# Schematic_SmartHome.net
KiCad netlist of a schematic drawn in EasyEDA
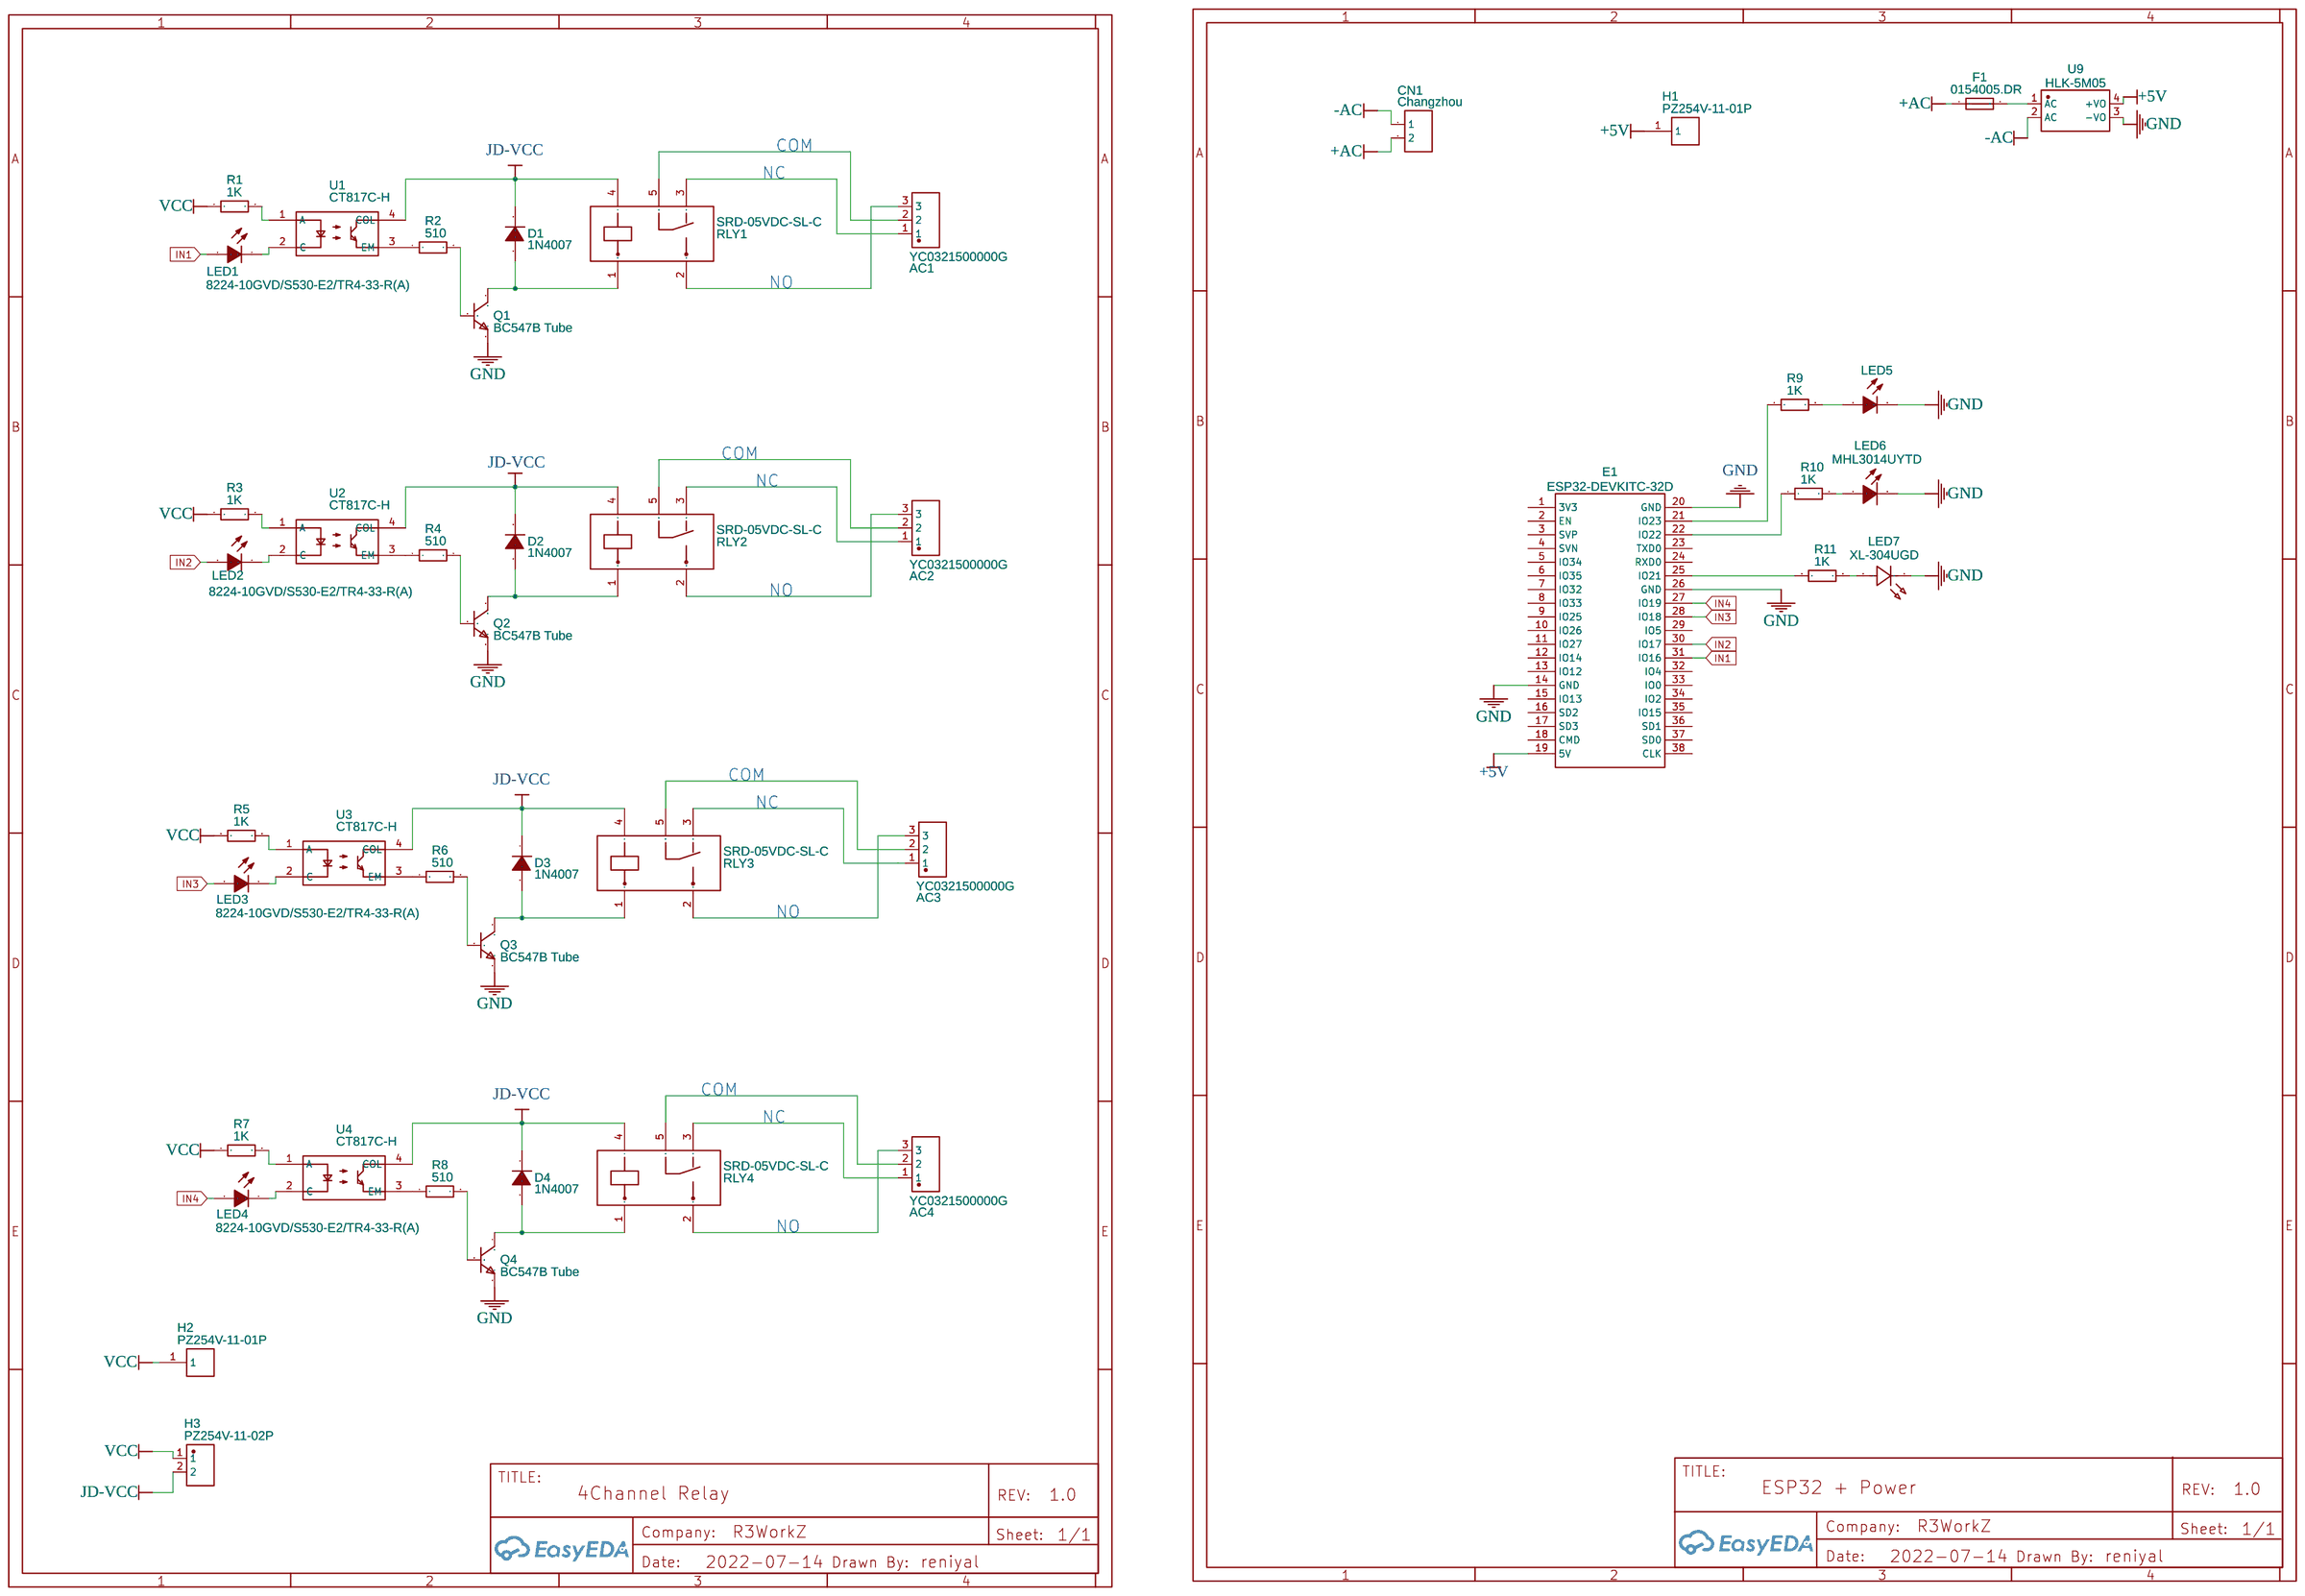
[diagram p0: schematic sheet]

(export (version "E")
  (design (tool "Eeschema 10.0.6"))
  (components
    (comp (ref "AC1")
      (value "YC0321500000G")
      (fields (field (name "BOM_Supplier Part") "C2683166"))
      (libsource (lib "") (part "YC0321500000G"))
    )
    (comp (ref "AC2")
      (value "YC0321500000G")
      (fields (field (name "BOM_Supplier Part") "C2683166"))
      (libsource (lib "") (part "YC0321500000G"))
    )
    (comp (ref "AC3")
      (value "YC0321500000G")
      (fields (field (name "BOM_Supplier Part") "C2683166"))
      (libsource (lib "") (part "YC0321500000G"))
    )
    (comp (ref "AC4")
      (value "YC0321500000G")
      (fields (field (name "BOM_Supplier Part") "C2683166"))
      (libsource (lib "") (part "YC0321500000G"))
    )
    (comp (ref "CN1")
      (value "Changzhou")
      (fields (field (name "BOM_Manufacturer Part") "XT30UPB-F") (field (name "BOM_Supplier Part") "C108769"))
      (libsource (lib "") (part "XT30UPB-F"))
    )
    (comp (ref "D1")
      (value "1N4007")
      (fields (field (name "BOM_Supplier Part") "C106903"))
      (libsource (lib "") (part "1N4007"))
    )
    (comp (ref "D2")
      (value "1N4007")
      (fields (field (name "BOM_Supplier Part") "C106903"))
      (libsource (lib "") (part "1N4007"))
    )
    (comp (ref "D3")
      (value "1N4007")
      (fields (field (name "BOM_Supplier Part") "C106903"))
      (libsource (lib "") (part "1N4007"))
    )
    (comp (ref "D4")
      (value "1N4007")
      (fields (field (name "BOM_Supplier Part") "C106903"))
      (libsource (lib "") (part "1N4007"))
    )
    (comp (ref "E1") (value "ESP32-DEVKITC-32D") (libsource (lib "") (part "ESP32-DEVKITC-32D")))
    (comp (ref "F1")
      (value "0154005.DR")
      (fields (field (name "BOM_Supplier Part") "C206916"))
      (libsource (lib "") (part "0154005.DR"))
    )
    (comp (ref "H1")
      (value "PZ254V-11-01P")
      (fields (field (name "BOM_Supplier Part") "C492400"))
      (libsource (lib "") (part "PZ254V-11-01P"))
    )
    (comp (ref "H2")
      (value "PZ254V-11-01P")
      (fields (field (name "BOM_Supplier Part") "C492400"))
      (libsource (lib "") (part "PZ254V-11-01P"))
    )
    (comp (ref "H3")
      (value "PZ254V-11-02P")
      (fields (field (name "BOM_Supplier Part") "C492401"))
      (libsource (lib "") (part "PZ254V-11-02P"))
    )
    (comp (ref "LED1")
      (value "8224-10GVD/S530-E2/TR4-33-R(A)")
      (fields (field (name "BOM_Supplier Part") "C329173"))
      (libsource (lib "") (part "8224-10GVD/S530-E2/TR4-33-R(A)"))
    )
    (comp (ref "LED2")
      (value "8224-10GVD/S530-E2/TR4-33-R(A)")
      (fields (field (name "BOM_Supplier Part") "C329173"))
      (libsource (lib "") (part "8224-10GVD/S530-E2/TR4-33-R(A)"))
    )
    (comp (ref "LED3")
      (value "8224-10GVD/S530-E2/TR4-33-R(A)")
      (fields (field (name "BOM_Supplier Part") "C329173"))
      (libsource (lib "") (part "8224-10GVD/S530-E2/TR4-33-R(A)"))
    )
    (comp (ref "LED4")
      (value "8224-10GVD/S530-E2/TR4-33-R(A)")
      (fields (field (name "BOM_Supplier Part") "C329173"))
      (libsource (lib "") (part "8224-10GVD/S530-E2/TR4-33-R(A)"))
    )
    (comp (ref "LED5")
      (value "8224-10GVD/S530-E2/TR4-33-R(A)")
      (fields (field (name "BOM_Supplier Part") "C329173"))
      (libsource (lib "") (part "8224-10GVD/S530-E2/TR4-33-R(A)"))
    )
    (comp (ref "LED6")
      (value "MHL3014UYTD")
      (fields (field (name "BOM_Supplier Part") "C409800"))
      (libsource (lib "") (part "MHL3014UYTD"))
    )
    (comp (ref "LED7")
      (value "XL-304UGD")
      (fields (field (name "BOM_Supplier Part") "C2895477"))
      (libsource (lib "") (part "XL-304UGD"))
    )
    (comp (ref "Q1")
      (value "BC547B Tube")
      (fields (field (name "BOM_Supplier Part") "C2092"))
      (libsource (lib "") (part "BC547B Tube"))
    )
    (comp (ref "Q2")
      (value "BC547B Tube")
      (fields (field (name "BOM_Supplier Part") "C2092"))
      (libsource (lib "") (part "BC547B Tube"))
    )
    (comp (ref "Q3")
      (value "BC547B Tube")
      (fields (field (name "BOM_Supplier Part") "C2092"))
      (libsource (lib "") (part "BC547B Tube"))
    )
    (comp (ref "Q4")
      (value "BC547B Tube")
      (fields (field (name "BOM_Supplier Part") "C2092"))
      (libsource (lib "") (part "BC547B Tube"))
    )
    (comp (ref "R1")
      (value "1K")
      (fields
        (field (name "BOM_Manufacturer Part") "MFR0W4F1001A50")
        (field (name "BOM_Supplier Part") "C57435")
      )
      (libsource (lib "") (part "MFR0W4F1001A50"))
    )
    (comp (ref "R2")
      (value "510")
      (fields
        (field (name "BOM_Manufacturer Part") "RNU18F5100A520NH")
        (field (name "BOM_Supplier Part") "C274431")
      )
      (libsource (lib "") (part "RNU18F5100A520NH"))
    )
    (comp (ref "R3")
      (value "1K")
      (fields
        (field (name "BOM_Manufacturer Part") "MFR0W4F1001A50")
        (field (name "BOM_Supplier Part") "C57435")
      )
      (libsource (lib "") (part "MFR0W4F1001A50"))
    )
    (comp (ref "R4")
      (value "510")
      (fields
        (field (name "BOM_Manufacturer Part") "RNU18F5100A520NH")
        (field (name "BOM_Supplier Part") "C274431")
      )
      (libsource (lib "") (part "RNU18F5100A520NH"))
    )
    (comp (ref "R5")
      (value "1K")
      (fields
        (field (name "BOM_Manufacturer Part") "MFR0W4F1001A50")
        (field (name "BOM_Supplier Part") "C57435")
      )
      (libsource (lib "") (part "MFR0W4F1001A50"))
    )
    (comp (ref "R6")
      (value "510")
      (fields
        (field (name "BOM_Manufacturer Part") "RNU18F5100A520NH")
        (field (name "BOM_Supplier Part") "C274431")
      )
      (libsource (lib "") (part "RNU18F5100A520NH"))
    )
    (comp (ref "R7")
      (value "1K")
      (fields
        (field (name "BOM_Manufacturer Part") "MFR0W4F1001A50")
        (field (name "BOM_Supplier Part") "C57435")
      )
      (libsource (lib "") (part "MFR0W4F1001A50"))
    )
    (comp (ref "R8")
      (value "510")
      (fields
        (field (name "BOM_Manufacturer Part") "RNU18F5100A520NH")
        (field (name "BOM_Supplier Part") "C274431")
      )
      (libsource (lib "") (part "RNU18F5100A520NH"))
    )
    (comp (ref "R9")
      (value "1K")
      (fields
        (field (name "BOM_Manufacturer Part") "MFR0W4F1001A50")
        (field (name "BOM_Supplier Part") "C57435")
      )
      (libsource (lib "") (part "MFR0W4F1001A50"))
    )
    (comp (ref "R10")
      (value "1K")
      (fields
        (field (name "BOM_Manufacturer Part") "MFR0W4F1001A50")
        (field (name "BOM_Supplier Part") "C57435")
      )
      (libsource (lib "") (part "MFR0W4F1001A50"))
    )
    (comp (ref "R11")
      (value "1K")
      (fields
        (field (name "BOM_Manufacturer Part") "MFR0W4F1001A50")
        (field (name "BOM_Supplier Part") "C57435")
      )
      (libsource (lib "") (part "MFR0W4F1001A50"))
    )
    (comp (ref "RLY1")
      (value "SRD-05VDC-SL-C")
      (fields (field (name "BOM_Supplier Part") "C35449"))
      (libsource (lib "") (part "SRD-05VDC-SL-C"))
    )
    (comp (ref "RLY2")
      (value "SRD-05VDC-SL-C")
      (fields (field (name "BOM_Supplier Part") "C35449"))
      (libsource (lib "") (part "SRD-05VDC-SL-C"))
    )
    (comp (ref "RLY3")
      (value "SRD-05VDC-SL-C")
      (fields (field (name "BOM_Supplier Part") "C35449"))
      (libsource (lib "") (part "SRD-05VDC-SL-C"))
    )
    (comp (ref "RLY4")
      (value "SRD-05VDC-SL-C")
      (fields (field (name "BOM_Supplier Part") "C35449"))
      (libsource (lib "") (part "SRD-05VDC-SL-C"))
    )
    (comp (ref "U1")
      (value "CT817C-H")
      (fields (field (name "BOM_Supplier Part") "C127188"))
      (libsource (lib "") (part "CT817C-H"))
    )
    (comp (ref "U2")
      (value "CT817C-H")
      (fields (field (name "BOM_Supplier Part") "C127188"))
      (libsource (lib "") (part "CT817C-H"))
    )
    (comp (ref "U3")
      (value "CT817C-H")
      (fields (field (name "BOM_Supplier Part") "C127188"))
      (libsource (lib "") (part "CT817C-H"))
    )
    (comp (ref "U4")
      (value "CT817C-H")
      (fields (field (name "BOM_Supplier Part") "C127188"))
      (libsource (lib "") (part "CT817C-H"))
    )
    (comp (ref "U9")
      (value "HLK-5M05")
      (fields (field (name "BOM_Supplier Part") "C209907"))
      (libsource (lib "") (part "HLK-5M05"))
    )
  )
  (nets
    (net (code "1") (name "+5V") (class "Default")
      (node (ref "E1") (pin "19") (pinfunction "5V_19") (pintype "unspecified"))
      (node (ref "H1") (pin "1") (pinfunction "1_1") (pintype "unspecified"))
      (node (ref "U9") (pin "4") (pinfunction "+VO_4") (pintype "unspecified"))
    )
    (net (code "2") (name "+AC") (class "Default")
      (node (ref "CN1") (pin "2") (pinfunction "2_2") (pintype "unspecified"))
      (node (ref "F1") (pin "1") (pinfunction "1_1") (pintype "unspecified"))
    )
    (net (code "3") (name "-AC") (class "Default")
      (node (ref "CN1") (pin "1") (pinfunction "1_1") (pintype "unspecified"))
      (node (ref "U9") (pin "2") (pinfunction "AC_2") (pintype "unspecified"))
    )
    (net (code "4") (name "GND") (class "Default")
      (node (ref "E1") (pin "14") (pinfunction "GND_14") (pintype "unspecified"))
      (node (ref "E1") (pin "20") (pinfunction "GND_20") (pintype "unspecified"))
      (node (ref "E1") (pin "26") (pinfunction "GND_26") (pintype "unspecified"))
      (node (ref "LED5") (pin "1") (pinfunction "K_1") (pintype "input"))
      (node (ref "LED6") (pin "2") (pinfunction "-_2") (pintype "unspecified"))
      (node (ref "LED7") (pin "2") (pinfunction "K_2") (pintype "unspecified"))
      (node (ref "Q1") (pin "3") (pinfunction "E_3") (pintype "unspecified"))
      (node (ref "Q2") (pin "3") (pinfunction "E_3") (pintype "unspecified"))
      (node (ref "Q3") (pin "3") (pinfunction "E_3") (pintype "unspecified"))
      (node (ref "Q4") (pin "3") (pinfunction "E_3") (pintype "unspecified"))
      (node (ref "U9") (pin "3") (pinfunction "-VO_3") (pintype "unspecified"))
    )
    (net (code "5") (name "IN1") (class "Default")
      (node (ref "E1") (pin "31") (pinfunction "IO16_31") (pintype "unspecified"))
      (node (ref "LED1") (pin "2") (pinfunction "A_2") (pintype "input"))
    )
    (net (code "6") (name "IN2") (class "Default")
      (node (ref "E1") (pin "30") (pinfunction "IO17_30") (pintype "unspecified"))
      (node (ref "LED2") (pin "2") (pinfunction "A_2") (pintype "input"))
    )
    (net (code "7") (name "IN3") (class "Default")
      (node (ref "E1") (pin "28") (pinfunction "IO18_28") (pintype "unspecified"))
      (node (ref "LED3") (pin "2") (pinfunction "A_2") (pintype "input"))
    )
    (net (code "8") (name "IN4") (class "Default")
      (node (ref "E1") (pin "27") (pinfunction "IO19_27") (pintype "unspecified"))
      (node (ref "LED4") (pin "2") (pinfunction "A_2") (pintype "input"))
    )
    (net (code "9") (name "JD-VCC") (class "Default")
      (node (ref "D1") (pin "1") (pinfunction "K_1") (pintype "unspecified"))
      (node (ref "D2") (pin "1") (pinfunction "K_1") (pintype "unspecified"))
      (node (ref "D3") (pin "1") (pinfunction "K_1") (pintype "unspecified"))
      (node (ref "D4") (pin "1") (pinfunction "K_1") (pintype "unspecified"))
      (node (ref "H3") (pin "2") (pinfunction "2_2") (pintype "unspecified"))
      (node (ref "RLY1") (pin "4") (pinfunction "4_4") (pintype "input"))
      (node (ref "RLY2") (pin "4") (pinfunction "4_4") (pintype "input"))
      (node (ref "RLY3") (pin "4") (pinfunction "4_4") (pintype "input"))
      (node (ref "RLY4") (pin "4") (pinfunction "4_4") (pintype "input"))
      (node (ref "U1") (pin "4") (pinfunction "COL_4") (pintype "unspecified"))
      (node (ref "U2") (pin "4") (pinfunction "COL_4") (pintype "unspecified"))
      (node (ref "U3") (pin "4") (pinfunction "COL_4") (pintype "unspecified"))
      (node (ref "U4") (pin "4") (pinfunction "COL_4") (pintype "unspecified"))
    )
    (net (code "10") (name "Net-(AC1-Pad1)") (class "Default")
      (node (ref "AC1") (pin "1") (pinfunction "1_1") (pintype "unspecified"))
      (node (ref "RLY1") (pin "3") (pinfunction "3_3") (pintype "input"))
    )
    (net (code "11") (name "Net-(AC1-Pad2)") (class "Default")
      (node (ref "AC1") (pin "2") (pinfunction "2_2") (pintype "unspecified"))
      (node (ref "RLY1") (pin "5") (pinfunction "5_5") (pintype "input"))
    )
    (net (code "12") (name "Net-(AC1-Pad3)") (class "Default")
      (node (ref "AC1") (pin "3") (pinfunction "3_3") (pintype "unspecified"))
      (node (ref "RLY1") (pin "2") (pinfunction "2_2") (pintype "input"))
    )
    (net (code "13") (name "Net-(AC2-Pad1)") (class "Default")
      (node (ref "AC2") (pin "1") (pinfunction "1_1") (pintype "unspecified"))
      (node (ref "RLY2") (pin "3") (pinfunction "3_3") (pintype "input"))
    )
    (net (code "14") (name "Net-(AC2-Pad2)") (class "Default")
      (node (ref "AC2") (pin "2") (pinfunction "2_2") (pintype "unspecified"))
      (node (ref "RLY2") (pin "5") (pinfunction "5_5") (pintype "input"))
    )
    (net (code "15") (name "Net-(AC2-Pad3)") (class "Default")
      (node (ref "AC2") (pin "3") (pinfunction "3_3") (pintype "unspecified"))
      (node (ref "RLY2") (pin "2") (pinfunction "2_2") (pintype "input"))
    )
    (net (code "16") (name "Net-(AC3-Pad1)") (class "Default")
      (node (ref "AC3") (pin "1") (pinfunction "1_1") (pintype "unspecified"))
      (node (ref "RLY3") (pin "3") (pinfunction "3_3") (pintype "input"))
    )
    (net (code "17") (name "Net-(AC3-Pad2)") (class "Default")
      (node (ref "AC3") (pin "2") (pinfunction "2_2") (pintype "unspecified"))
      (node (ref "RLY3") (pin "5") (pinfunction "5_5") (pintype "input"))
    )
    (net (code "18") (name "Net-(AC3-Pad3)") (class "Default")
      (node (ref "AC3") (pin "3") (pinfunction "3_3") (pintype "unspecified"))
      (node (ref "RLY3") (pin "2") (pinfunction "2_2") (pintype "input"))
    )
    (net (code "19") (name "Net-(AC4-Pad1)") (class "Default")
      (node (ref "AC4") (pin "1") (pinfunction "1_1") (pintype "unspecified"))
      (node (ref "RLY4") (pin "3") (pinfunction "3_3") (pintype "input"))
    )
    (net (code "20") (name "Net-(AC4-Pad2)") (class "Default")
      (node (ref "AC4") (pin "2") (pinfunction "2_2") (pintype "unspecified"))
      (node (ref "RLY4") (pin "5") (pinfunction "5_5") (pintype "input"))
    )
    (net (code "21") (name "Net-(AC4-Pad3)") (class "Default")
      (node (ref "AC4") (pin "3") (pinfunction "3_3") (pintype "unspecified"))
      (node (ref "RLY4") (pin "2") (pinfunction "2_2") (pintype "input"))
    )
    (net (code "22") (name "Net-(D1-A)") (class "Default")
      (node (ref "D1") (pin "2") (pinfunction "A_2") (pintype "unspecified"))
      (node (ref "Q1") (pin "1") (pinfunction "C_1") (pintype "unspecified"))
      (node (ref "RLY1") (pin "1") (pinfunction "1_1") (pintype "input"))
    )
    (net (code "23") (name "Net-(D2-A)") (class "Default")
      (node (ref "D2") (pin "2") (pinfunction "A_2") (pintype "unspecified"))
      (node (ref "Q2") (pin "1") (pinfunction "C_1") (pintype "unspecified"))
      (node (ref "RLY2") (pin "1") (pinfunction "1_1") (pintype "input"))
    )
    (net (code "24") (name "Net-(D3-A)") (class "Default")
      (node (ref "D3") (pin "2") (pinfunction "A_2") (pintype "unspecified"))
      (node (ref "Q3") (pin "1") (pinfunction "C_1") (pintype "unspecified"))
      (node (ref "RLY3") (pin "1") (pinfunction "1_1") (pintype "input"))
    )
    (net (code "25") (name "Net-(D4-A)") (class "Default")
      (node (ref "D4") (pin "2") (pinfunction "A_2") (pintype "unspecified"))
      (node (ref "Q4") (pin "1") (pinfunction "C_1") (pintype "unspecified"))
      (node (ref "RLY4") (pin "1") (pinfunction "1_1") (pintype "input"))
    )
    (net (code "26") (name "Net-(E1-IO21)") (class "Default")
      (node (ref "E1") (pin "25") (pinfunction "IO21_25") (pintype "unspecified"))
      (node (ref "R11") (pin "1") (pinfunction "1_1") (pintype "input"))
    )
    (net (code "27") (name "Net-(E1-IO22)") (class "Default")
      (node (ref "E1") (pin "22") (pinfunction "IO22_22") (pintype "unspecified"))
      (node (ref "R10") (pin "1") (pinfunction "1_1") (pintype "input"))
    )
    (net (code "28") (name "Net-(E1-IO23)") (class "Default")
      (node (ref "E1") (pin "21") (pinfunction "IO23_21") (pintype "unspecified"))
      (node (ref "R9") (pin "1") (pinfunction "1_1") (pintype "input"))
    )
    (net (code "29") (name "Net-(F1-Pad2)") (class "Default")
      (node (ref "F1") (pin "2") (pinfunction "2_2") (pintype "unspecified"))
      (node (ref "U9") (pin "1") (pinfunction "AC_1") (pintype "unspecified"))
    )
    (net (code "30") (name "Net-(LED1-K)") (class "Default")
      (node (ref "LED1") (pin "1") (pinfunction "K_1") (pintype "input"))
      (node (ref "U1") (pin "2") (pinfunction "C_2") (pintype "unspecified"))
    )
    (net (code "31") (name "Net-(LED2-K)") (class "Default")
      (node (ref "LED2") (pin "1") (pinfunction "K_1") (pintype "input"))
      (node (ref "U2") (pin "2") (pinfunction "C_2") (pintype "unspecified"))
    )
    (net (code "32") (name "Net-(LED3-K)") (class "Default")
      (node (ref "LED3") (pin "1") (pinfunction "K_1") (pintype "input"))
      (node (ref "U3") (pin "2") (pinfunction "C_2") (pintype "unspecified"))
    )
    (net (code "33") (name "Net-(LED4-K)") (class "Default")
      (node (ref "LED4") (pin "1") (pinfunction "K_1") (pintype "input"))
      (node (ref "U4") (pin "2") (pinfunction "C_2") (pintype "unspecified"))
    )
    (net (code "34") (name "Net-(LED5-A)") (class "Default")
      (node (ref "LED5") (pin "2") (pinfunction "A_2") (pintype "input"))
      (node (ref "R9") (pin "2") (pinfunction "2_2") (pintype "input"))
    )
    (net (code "35") (name "Net-(LED6-+)") (class "Default")
      (node (ref "LED6") (pin "1") (pinfunction "+_1") (pintype "unspecified"))
      (node (ref "R10") (pin "2") (pinfunction "2_2") (pintype "input"))
    )
    (net (code "36") (name "Net-(LED7-A)") (class "Default")
      (node (ref "LED7") (pin "1") (pinfunction "A_1") (pintype "unspecified"))
      (node (ref "R11") (pin "2") (pinfunction "2_2") (pintype "input"))
    )
    (net (code "37") (name "Net-(Q1-B)") (class "Default")
      (node (ref "Q1") (pin "2") (pinfunction "B_2") (pintype "unspecified"))
      (node (ref "R2") (pin "2") (pinfunction "2_2") (pintype "unspecified"))
    )
    (net (code "38") (name "Net-(Q2-B)") (class "Default")
      (node (ref "Q2") (pin "2") (pinfunction "B_2") (pintype "unspecified"))
      (node (ref "R4") (pin "2") (pinfunction "2_2") (pintype "unspecified"))
    )
    (net (code "39") (name "Net-(Q3-B)") (class "Default")
      (node (ref "Q3") (pin "2") (pinfunction "B_2") (pintype "unspecified"))
      (node (ref "R6") (pin "2") (pinfunction "2_2") (pintype "unspecified"))
    )
    (net (code "40") (name "Net-(Q4-B)") (class "Default")
      (node (ref "Q4") (pin "2") (pinfunction "B_2") (pintype "unspecified"))
      (node (ref "R8") (pin "2") (pinfunction "2_2") (pintype "unspecified"))
    )
    (net (code "41") (name "Net-(U1-A)") (class "Default")
      (node (ref "R1") (pin "2") (pinfunction "2_2") (pintype "input"))
      (node (ref "U1") (pin "1") (pinfunction "A_1") (pintype "unspecified"))
    )
    (net (code "42") (name "Net-(U1-EM)") (class "Default")
      (node (ref "R2") (pin "1") (pinfunction "1_1") (pintype "unspecified"))
      (node (ref "U1") (pin "3") (pinfunction "EM_3") (pintype "unspecified"))
    )
    (net (code "43") (name "Net-(U2-A)") (class "Default")
      (node (ref "R3") (pin "2") (pinfunction "2_2") (pintype "input"))
      (node (ref "U2") (pin "1") (pinfunction "A_1") (pintype "unspecified"))
    )
    (net (code "44") (name "Net-(U2-EM)") (class "Default")
      (node (ref "R4") (pin "1") (pinfunction "1_1") (pintype "unspecified"))
      (node (ref "U2") (pin "3") (pinfunction "EM_3") (pintype "unspecified"))
    )
    (net (code "45") (name "Net-(U3-A)") (class "Default")
      (node (ref "R5") (pin "2") (pinfunction "2_2") (pintype "input"))
      (node (ref "U3") (pin "1") (pinfunction "A_1") (pintype "unspecified"))
    )
    (net (code "46") (name "Net-(U3-EM)") (class "Default")
      (node (ref "R6") (pin "1") (pinfunction "1_1") (pintype "unspecified"))
      (node (ref "U3") (pin "3") (pinfunction "EM_3") (pintype "unspecified"))
    )
    (net (code "47") (name "Net-(U4-A)") (class "Default")
      (node (ref "R7") (pin "2") (pinfunction "2_2") (pintype "input"))
      (node (ref "U4") (pin "1") (pinfunction "A_1") (pintype "unspecified"))
    )
    (net (code "48") (name "Net-(U4-EM)") (class "Default")
      (node (ref "R8") (pin "1") (pinfunction "1_1") (pintype "unspecified"))
      (node (ref "U4") (pin "3") (pinfunction "EM_3") (pintype "unspecified"))
    )
    (net (code "49") (name "VCC") (class "Default")
      (node (ref "H2") (pin "1") (pinfunction "1_1") (pintype "unspecified"))
      (node (ref "H3") (pin "1") (pinfunction "1_1") (pintype "unspecified"))
      (node (ref "R1") (pin "1") (pinfunction "1_1") (pintype "input"))
      (node (ref "R3") (pin "1") (pinfunction "1_1") (pintype "input"))
      (node (ref "R5") (pin "1") (pinfunction "1_1") (pintype "input"))
      (node (ref "R7") (pin "1") (pinfunction "1_1") (pintype "input"))
    )
    (net (code "50") (name "unconnected-(E1-3V3-Pad1)") (class "Default")
      (node (ref "E1") (pin "1") (pinfunction "3V3_1") (pintype "unspecified"))
    )
    (net (code "51") (name "unconnected-(E1-CLK-Pad38)") (class "Default")
      (node (ref "E1") (pin "38") (pinfunction "CLK_38") (pintype "unspecified"))
    )
    (net (code "52") (name "unconnected-(E1-CMD-Pad18)") (class "Default")
      (node (ref "E1") (pin "18") (pinfunction "CMD_18") (pintype "unspecified"))
    )
    (net (code "53") (name "unconnected-(E1-EN-Pad2)") (class "Default")
      (node (ref "E1") (pin "2") (pinfunction "EN_2") (pintype "unspecified"))
    )
    (net (code "54") (name "unconnected-(E1-IO0-Pad33)") (class "Default")
      (node (ref "E1") (pin "33") (pinfunction "IO0_33") (pintype "unspecified"))
    )
    (net (code "55") (name "unconnected-(E1-IO2-Pad34)") (class "Default")
      (node (ref "E1") (pin "34") (pinfunction "IO2_34") (pintype "unspecified"))
    )
    (net (code "56") (name "unconnected-(E1-IO4-Pad32)") (class "Default")
      (node (ref "E1") (pin "32") (pinfunction "IO4_32") (pintype "unspecified"))
    )
    (net (code "57") (name "unconnected-(E1-IO5-Pad29)") (class "Default")
      (node (ref "E1") (pin "29") (pinfunction "IO5_29") (pintype "unspecified"))
    )
    (net (code "58") (name "unconnected-(E1-IO12-Pad13)") (class "Default")
      (node (ref "E1") (pin "13") (pinfunction "IO12_13") (pintype "unspecified"))
    )
    (net (code "59") (name "unconnected-(E1-IO13-Pad15)") (class "Default")
      (node (ref "E1") (pin "15") (pinfunction "IO13_15") (pintype "unspecified"))
    )
    (net (code "60") (name "unconnected-(E1-IO14-Pad12)") (class "Default")
      (node (ref "E1") (pin "12") (pinfunction "IO14_12") (pintype "unspecified"))
    )
    (net (code "61") (name "unconnected-(E1-IO15-Pad35)") (class "Default")
      (node (ref "E1") (pin "35") (pinfunction "IO15_35") (pintype "unspecified"))
    )
    (net (code "62") (name "unconnected-(E1-IO25-Pad9)") (class "Default")
      (node (ref "E1") (pin "9") (pinfunction "IO25_9") (pintype "unspecified"))
    )
    (net (code "63") (name "unconnected-(E1-IO26-Pad10)") (class "Default")
      (node (ref "E1") (pin "10") (pinfunction "IO26_10") (pintype "unspecified"))
    )
    (net (code "64") (name "unconnected-(E1-IO27-Pad11)") (class "Default")
      (node (ref "E1") (pin "11") (pinfunction "IO27_11") (pintype "unspecified"))
    )
    (net (code "65") (name "unconnected-(E1-IO32-Pad7)") (class "Default")
      (node (ref "E1") (pin "7") (pinfunction "IO32_7") (pintype "unspecified"))
    )
    (net (code "66") (name "unconnected-(E1-IO33-Pad8)") (class "Default")
      (node (ref "E1") (pin "8") (pinfunction "IO33_8") (pintype "unspecified"))
    )
    (net (code "67") (name "unconnected-(E1-IO34-Pad5)") (class "Default")
      (node (ref "E1") (pin "5") (pinfunction "IO34_5") (pintype "unspecified"))
    )
    (net (code "68") (name "unconnected-(E1-IO35-Pad6)") (class "Default")
      (node (ref "E1") (pin "6") (pinfunction "IO35_6") (pintype "unspecified"))
    )
    (net (code "69") (name "unconnected-(E1-RXD0-Pad24)") (class "Default")
      (node (ref "E1") (pin "24") (pinfunction "RXD0_24") (pintype "unspecified"))
    )
    (net (code "70") (name "unconnected-(E1-SD0-Pad37)") (class "Default")
      (node (ref "E1") (pin "37") (pinfunction "SD0_37") (pintype "unspecified"))
    )
    (net (code "71") (name "unconnected-(E1-SD1-Pad36)") (class "Default")
      (node (ref "E1") (pin "36") (pinfunction "SD1_36") (pintype "unspecified"))
    )
    (net (code "72") (name "unconnected-(E1-SD2-Pad16)") (class "Default")
      (node (ref "E1") (pin "16") (pinfunction "SD2_16") (pintype "unspecified"))
    )
    (net (code "73") (name "unconnected-(E1-SD3-Pad17)") (class "Default")
      (node (ref "E1") (pin "17") (pinfunction "SD3_17") (pintype "unspecified"))
    )
    (net (code "74") (name "unconnected-(E1-SVN-Pad4)") (class "Default")
      (node (ref "E1") (pin "4") (pinfunction "SVN_4") (pintype "unspecified"))
    )
    (net (code "75") (name "unconnected-(E1-SVP-Pad3)") (class "Default")
      (node (ref "E1") (pin "3") (pinfunction "SVP_3") (pintype "unspecified"))
    )
    (net (code "76") (name "unconnected-(E1-TXD0-Pad23)") (class "Default")
      (node (ref "E1") (pin "23") (pinfunction "TXD0_23") (pintype "unspecified"))
    )
  )
)
